# Daisy.net
KiCad netlist of a schematic drawn in EasyEDA Pro
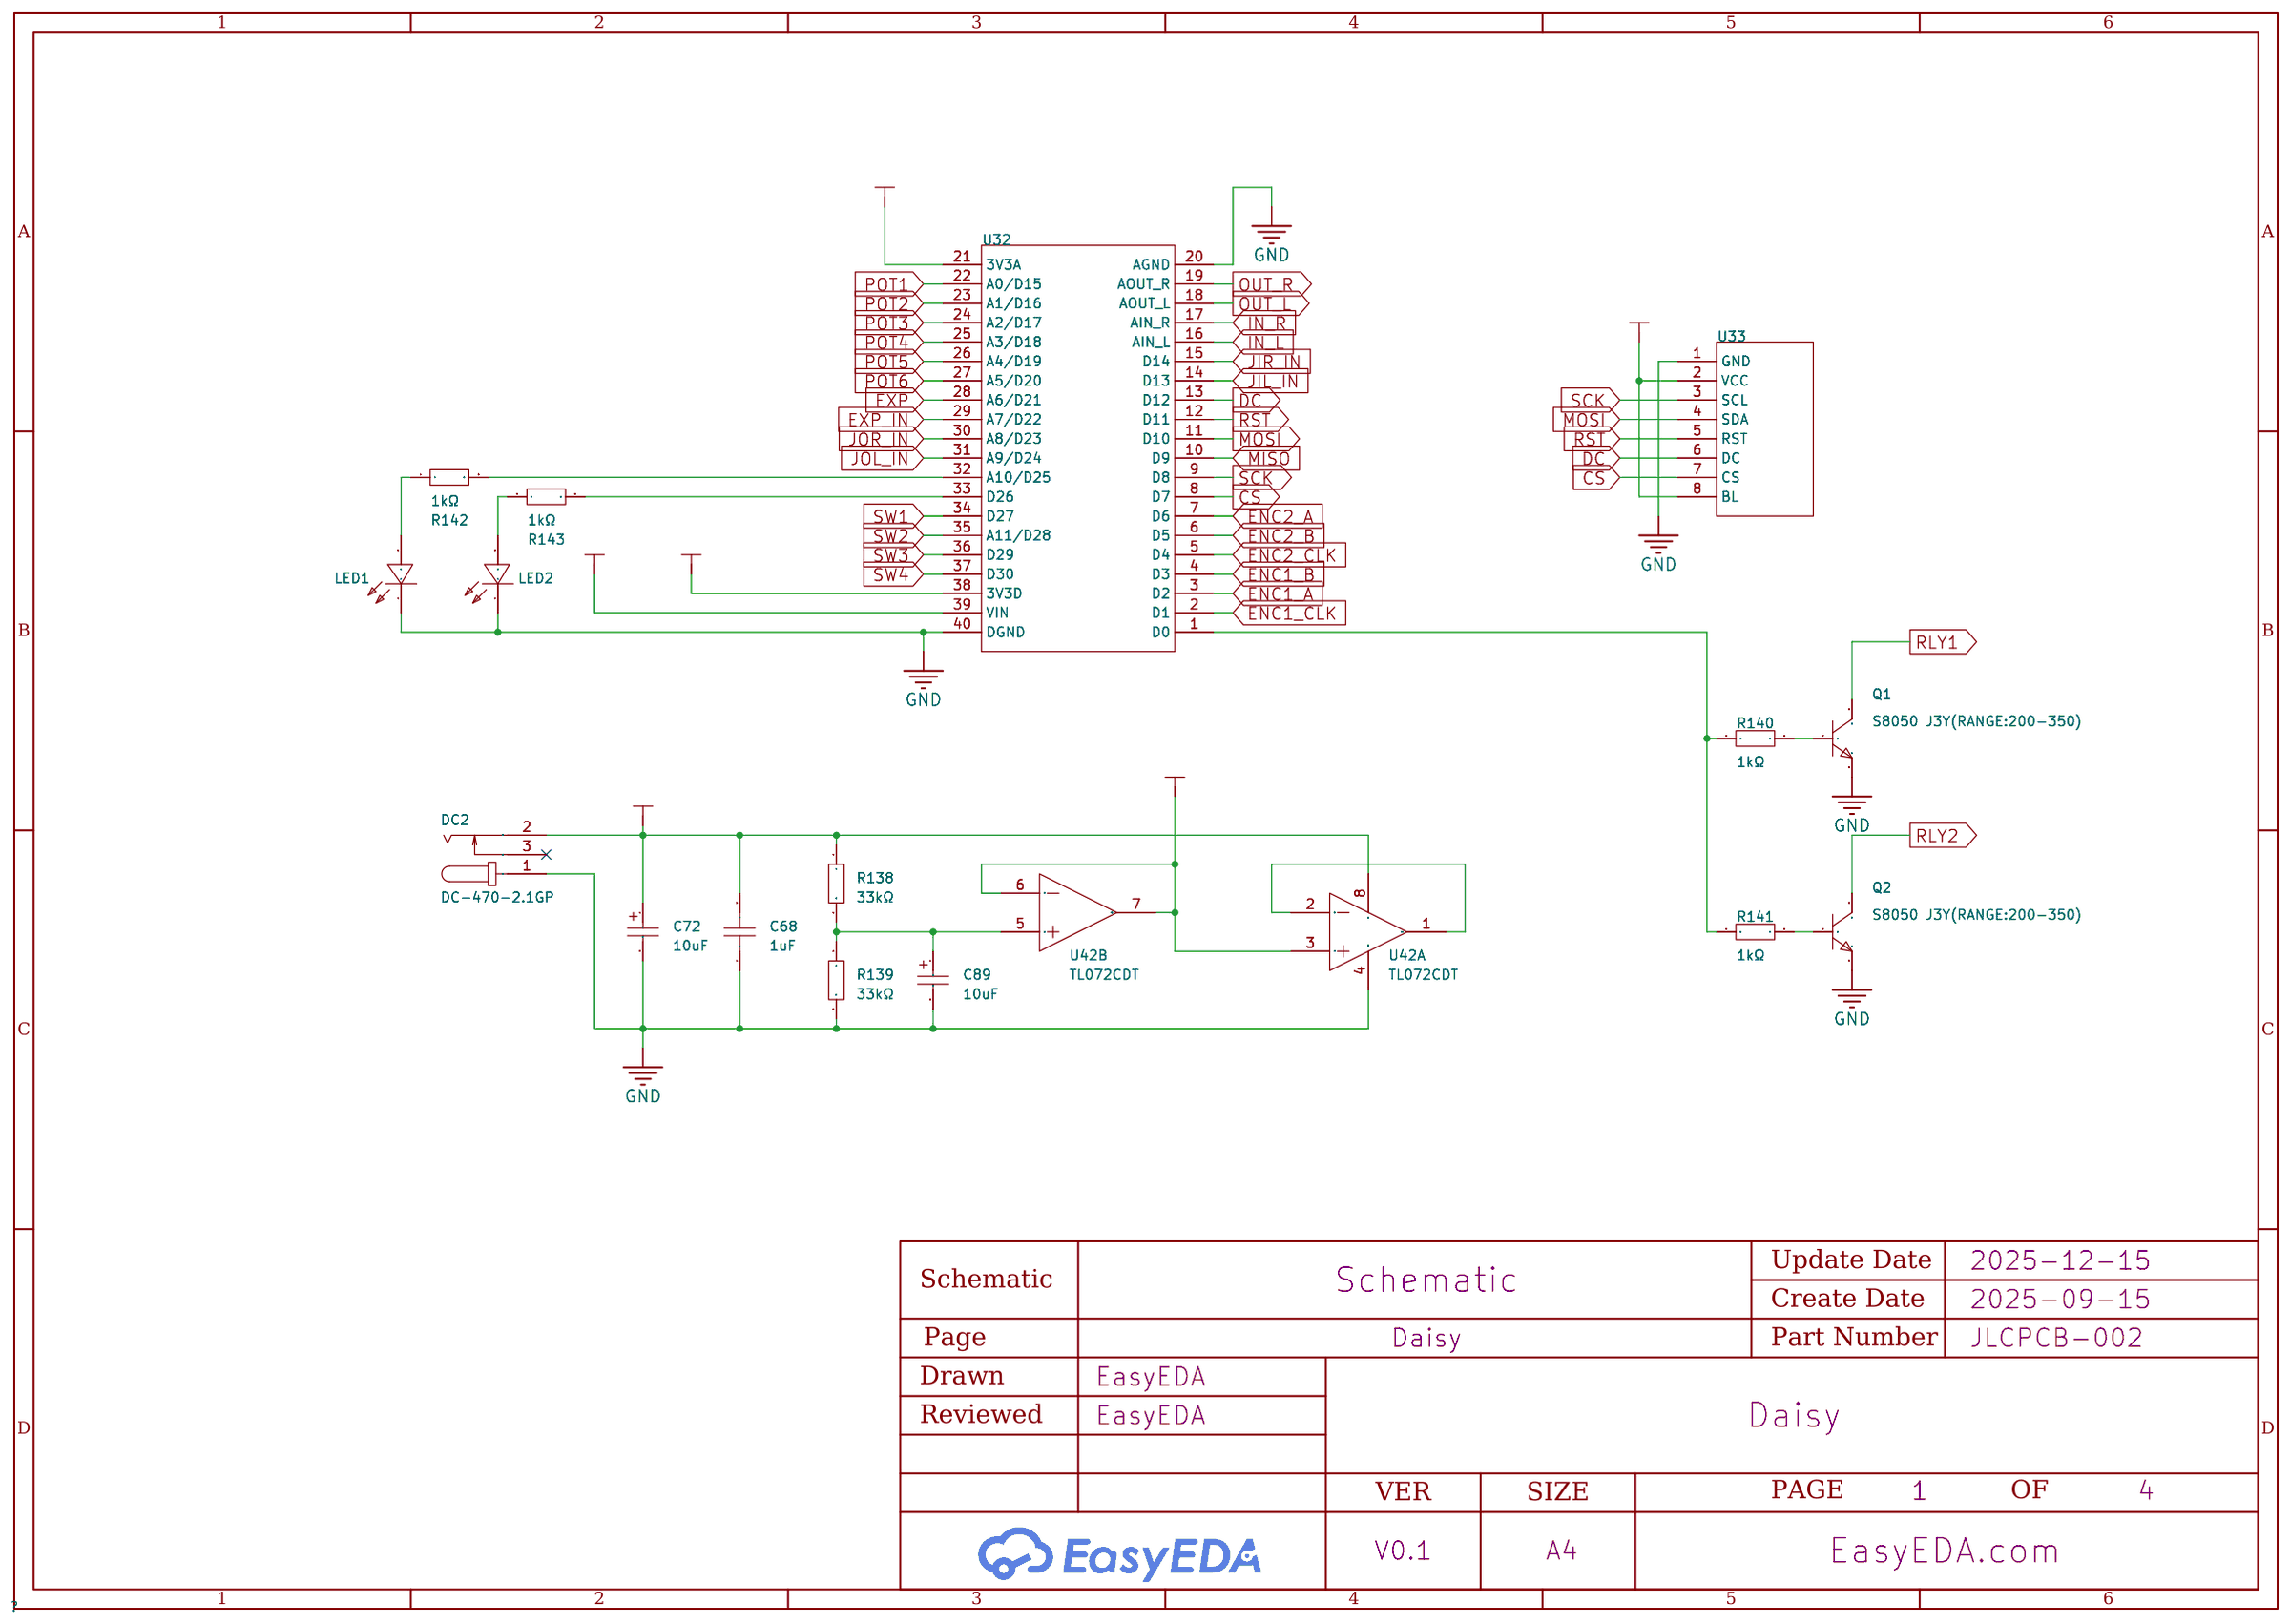
[diagram p0: Daisy]
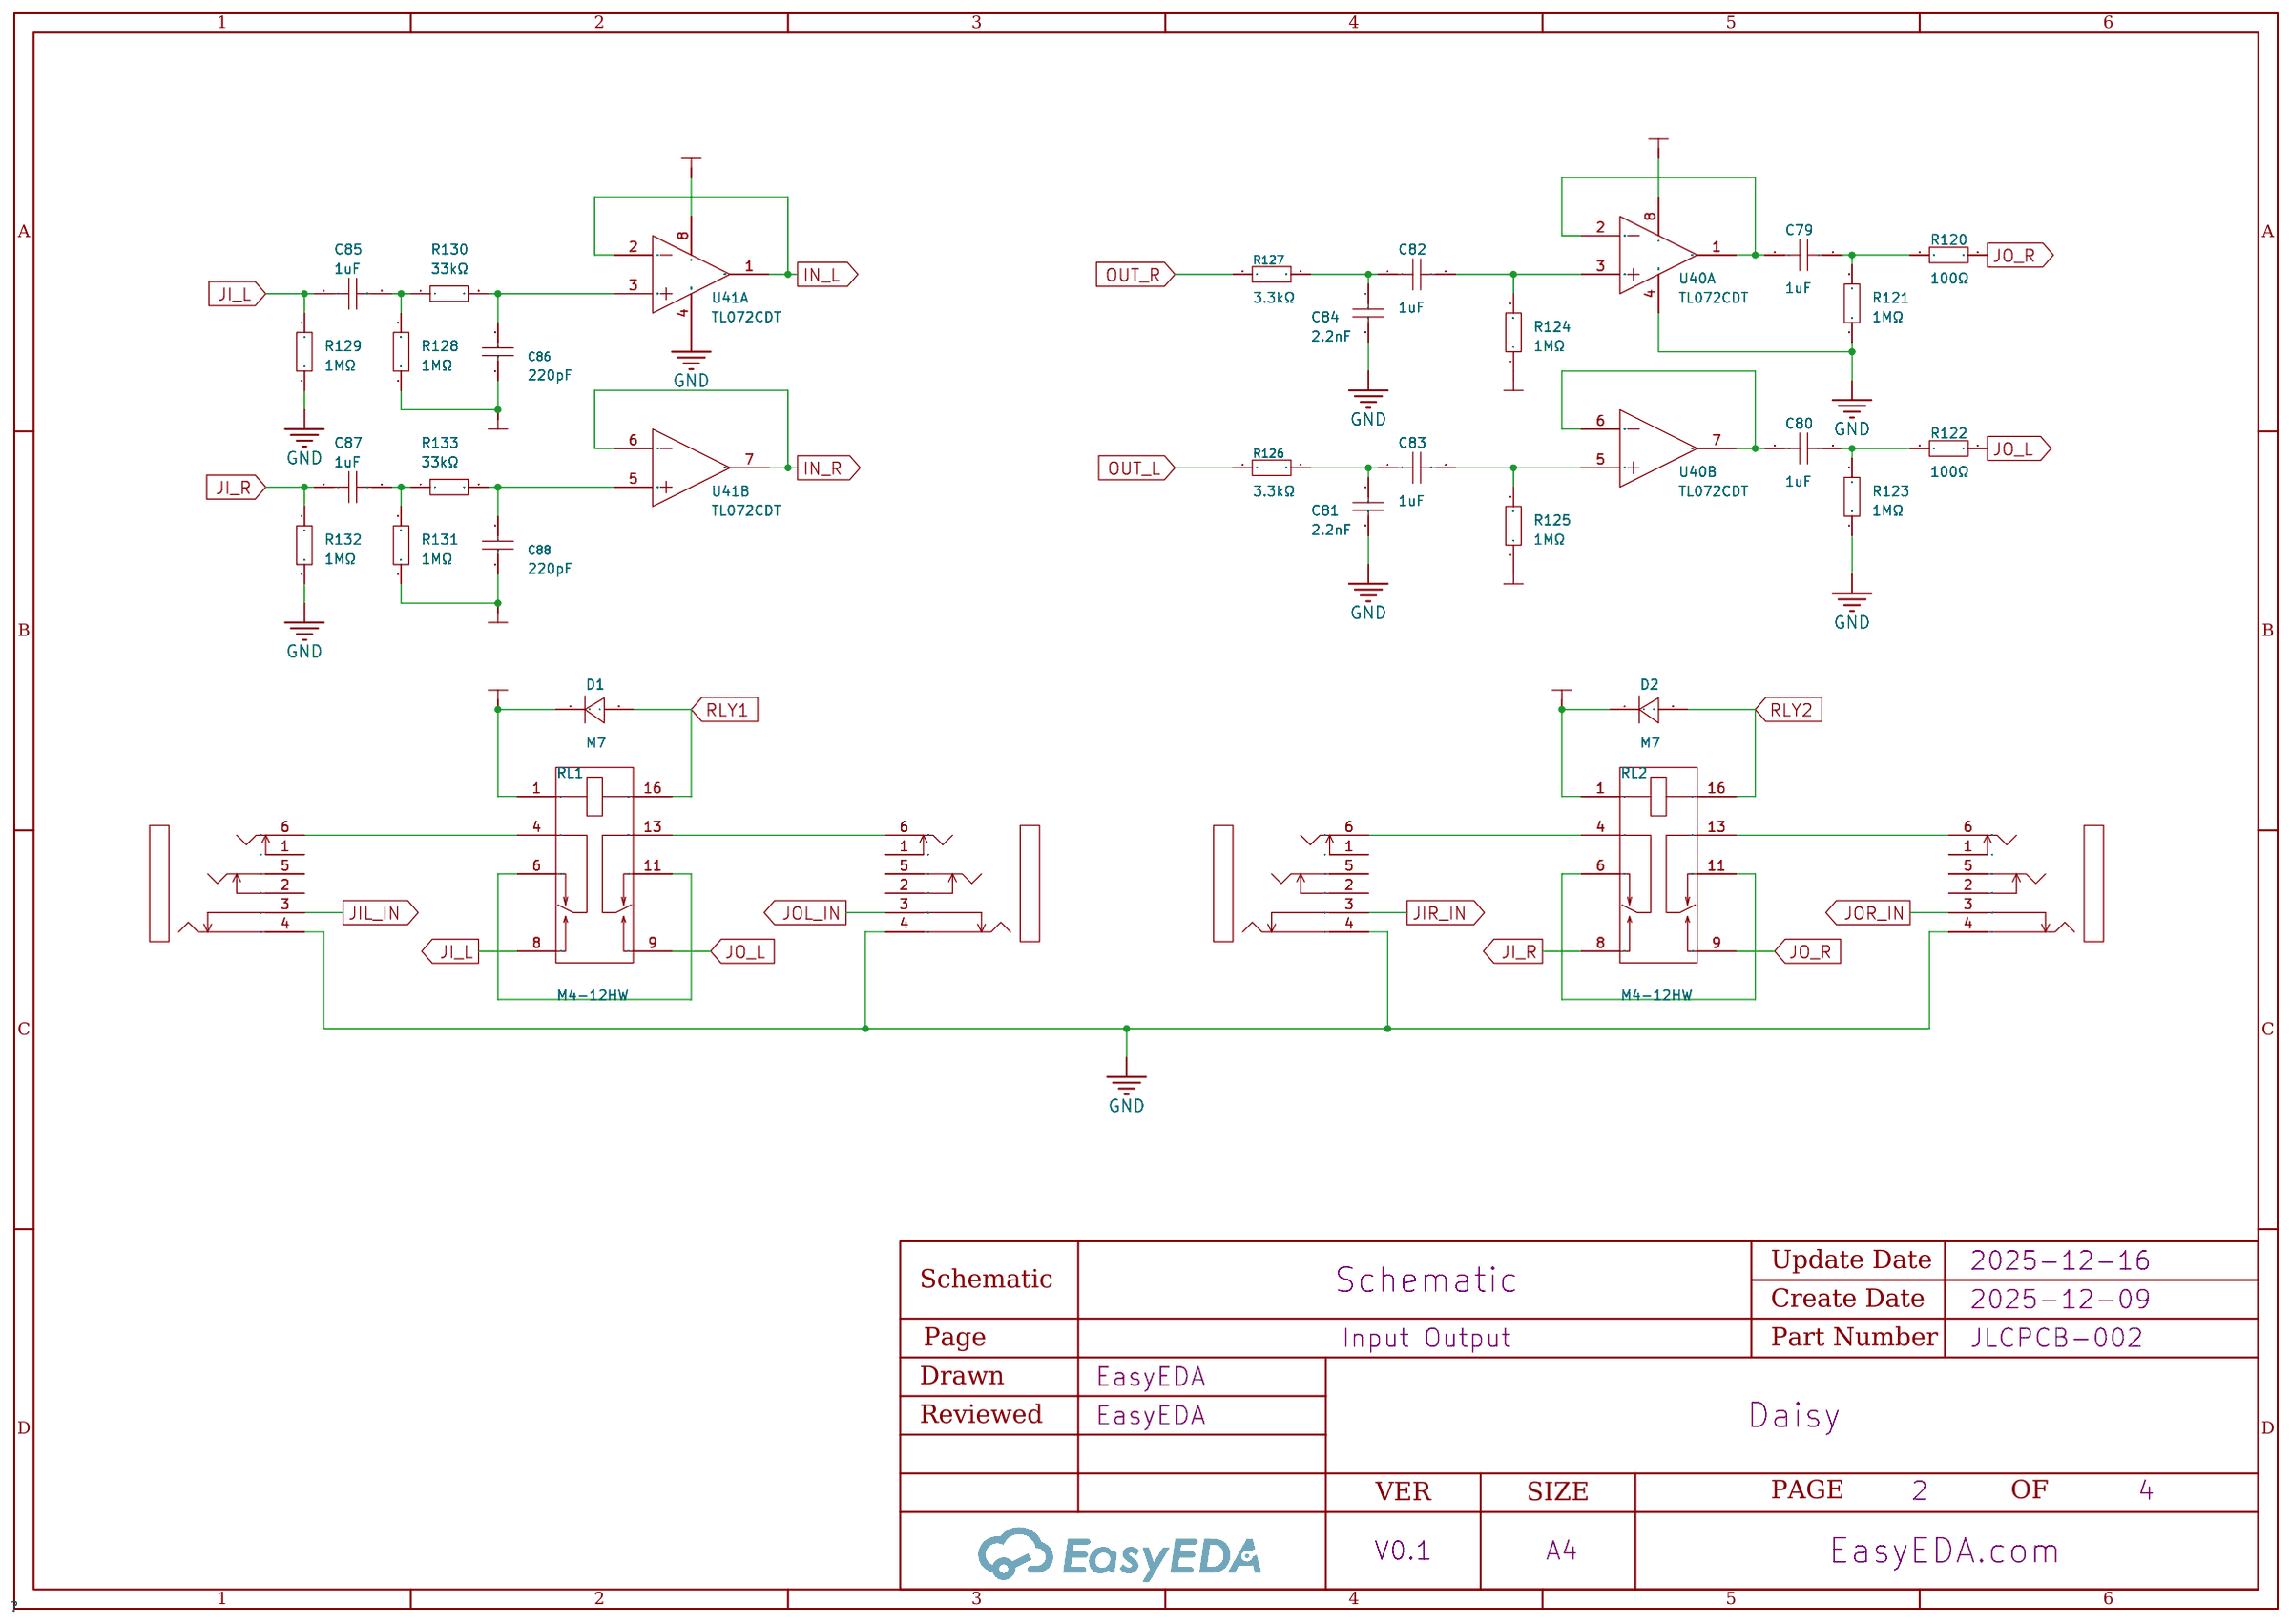
[diagram p1: Input Output]
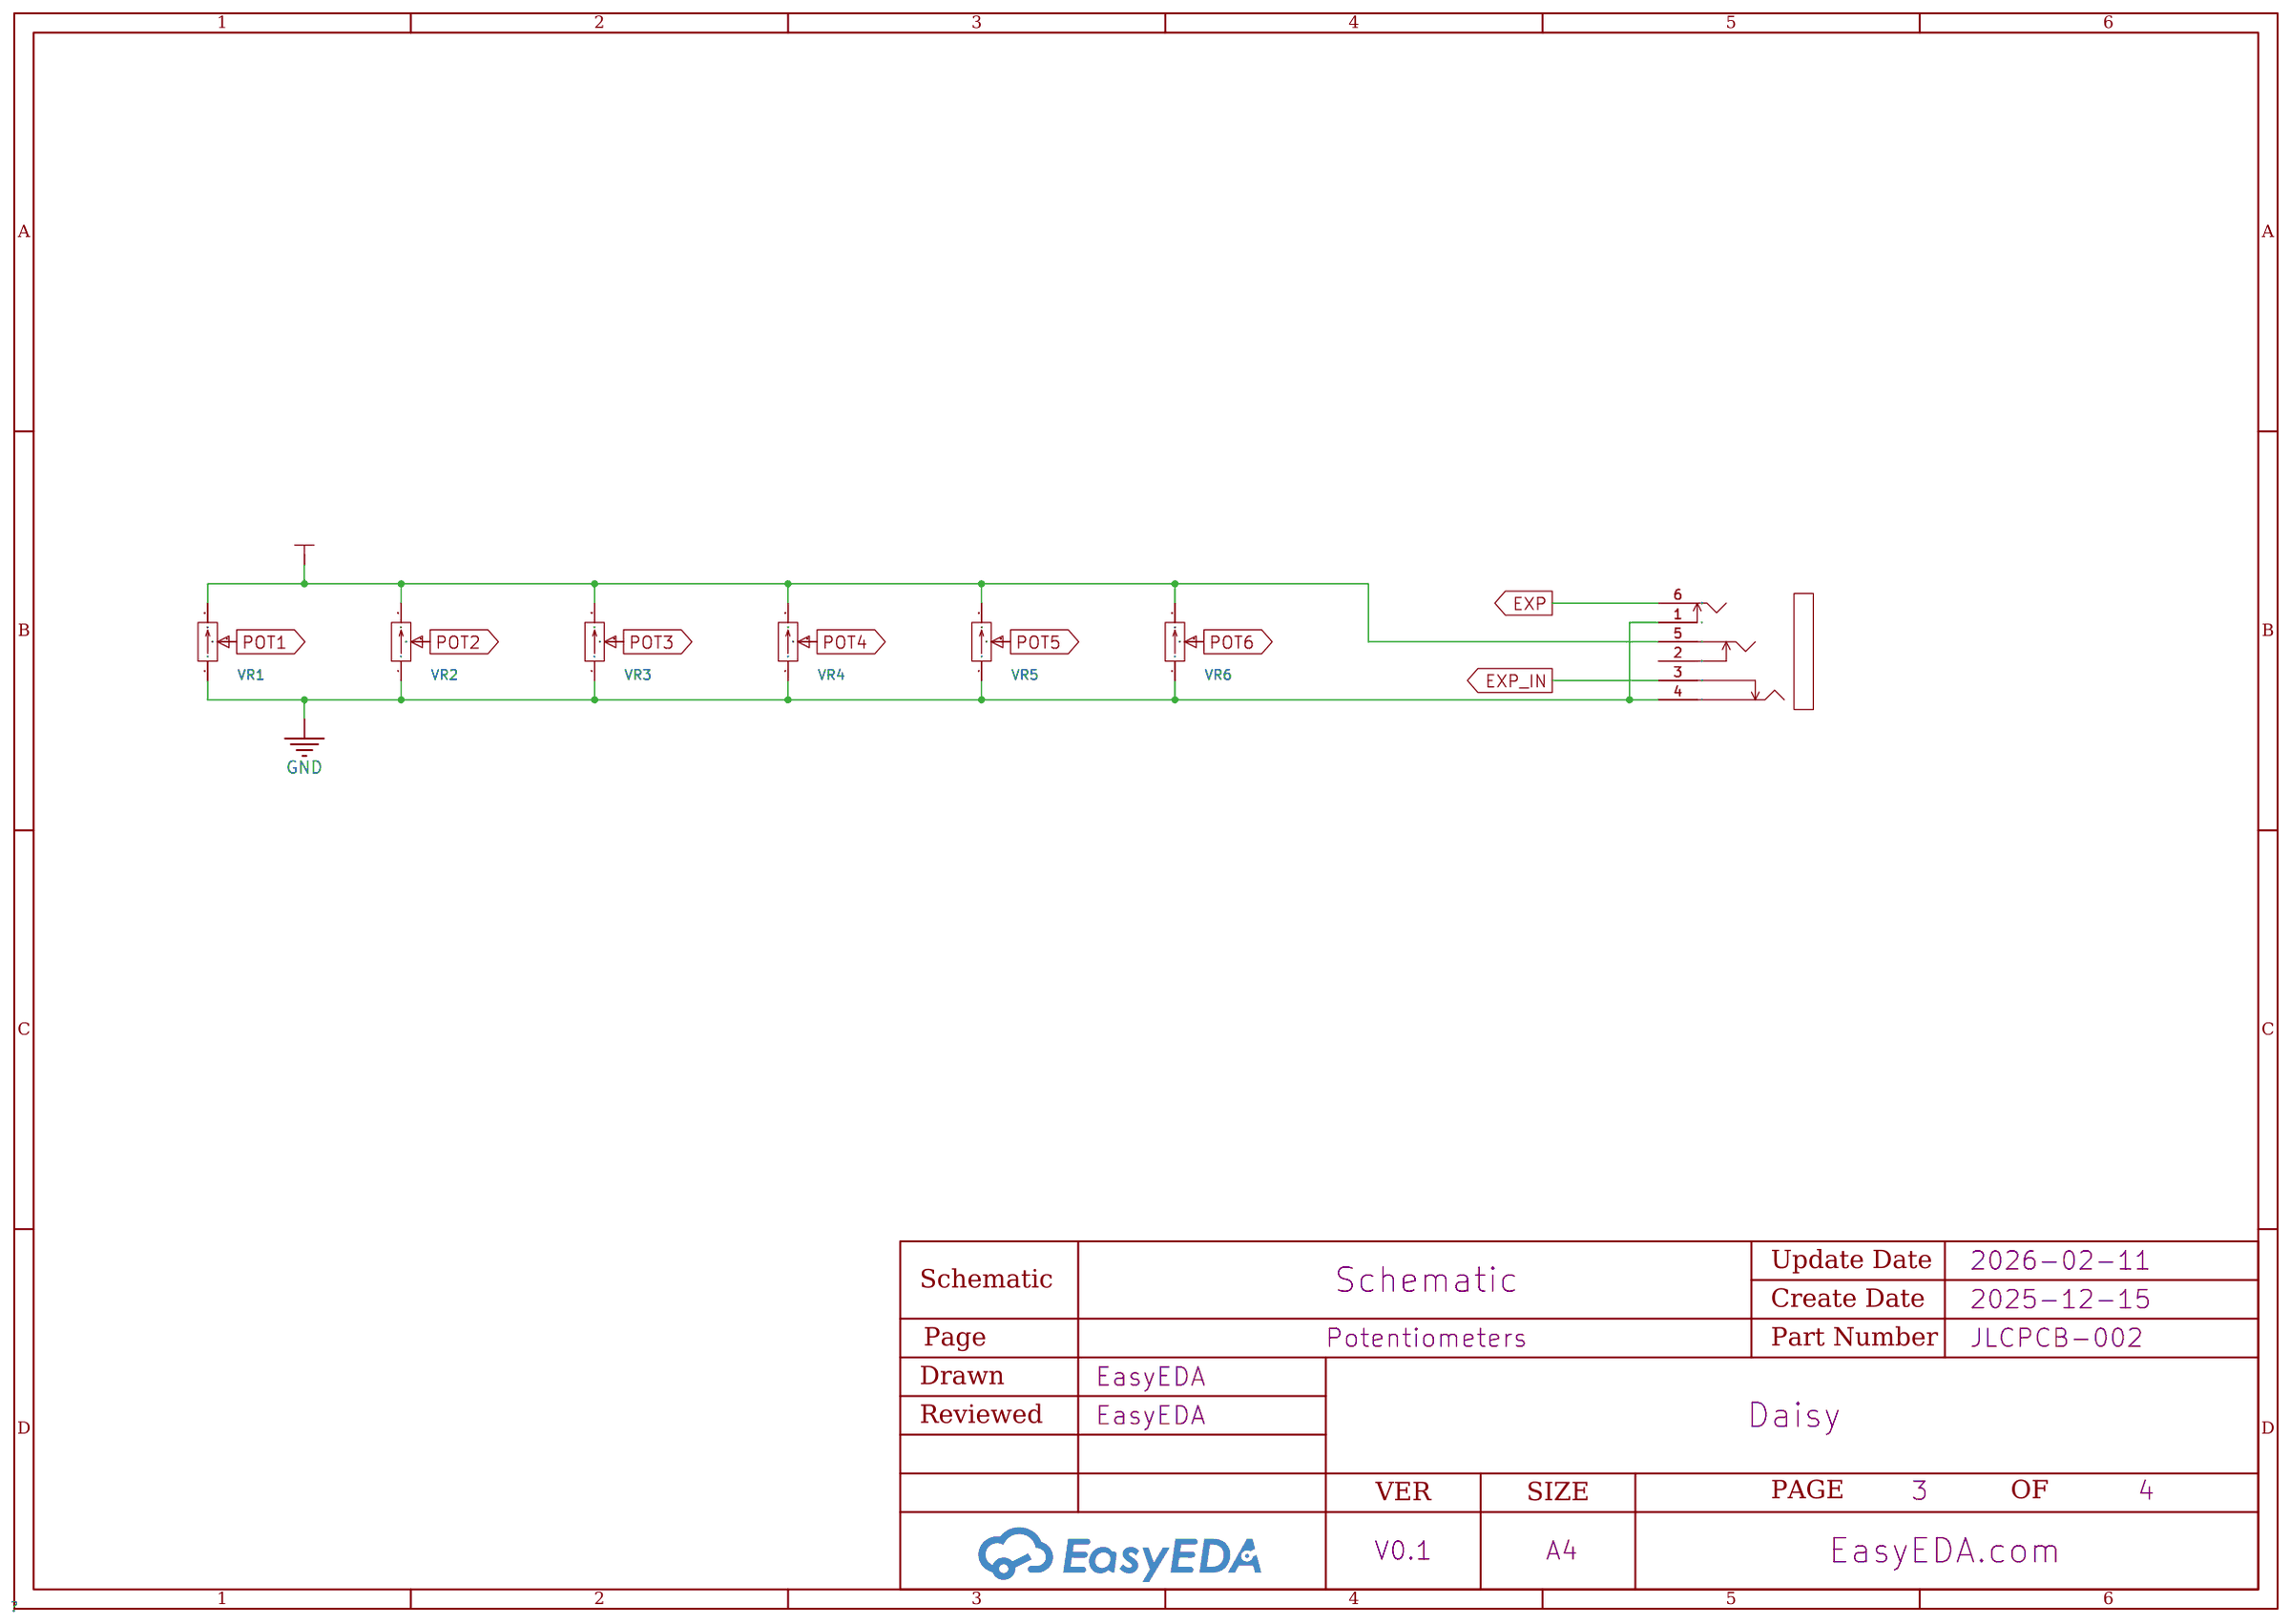
[diagram p2: Potentiometers]
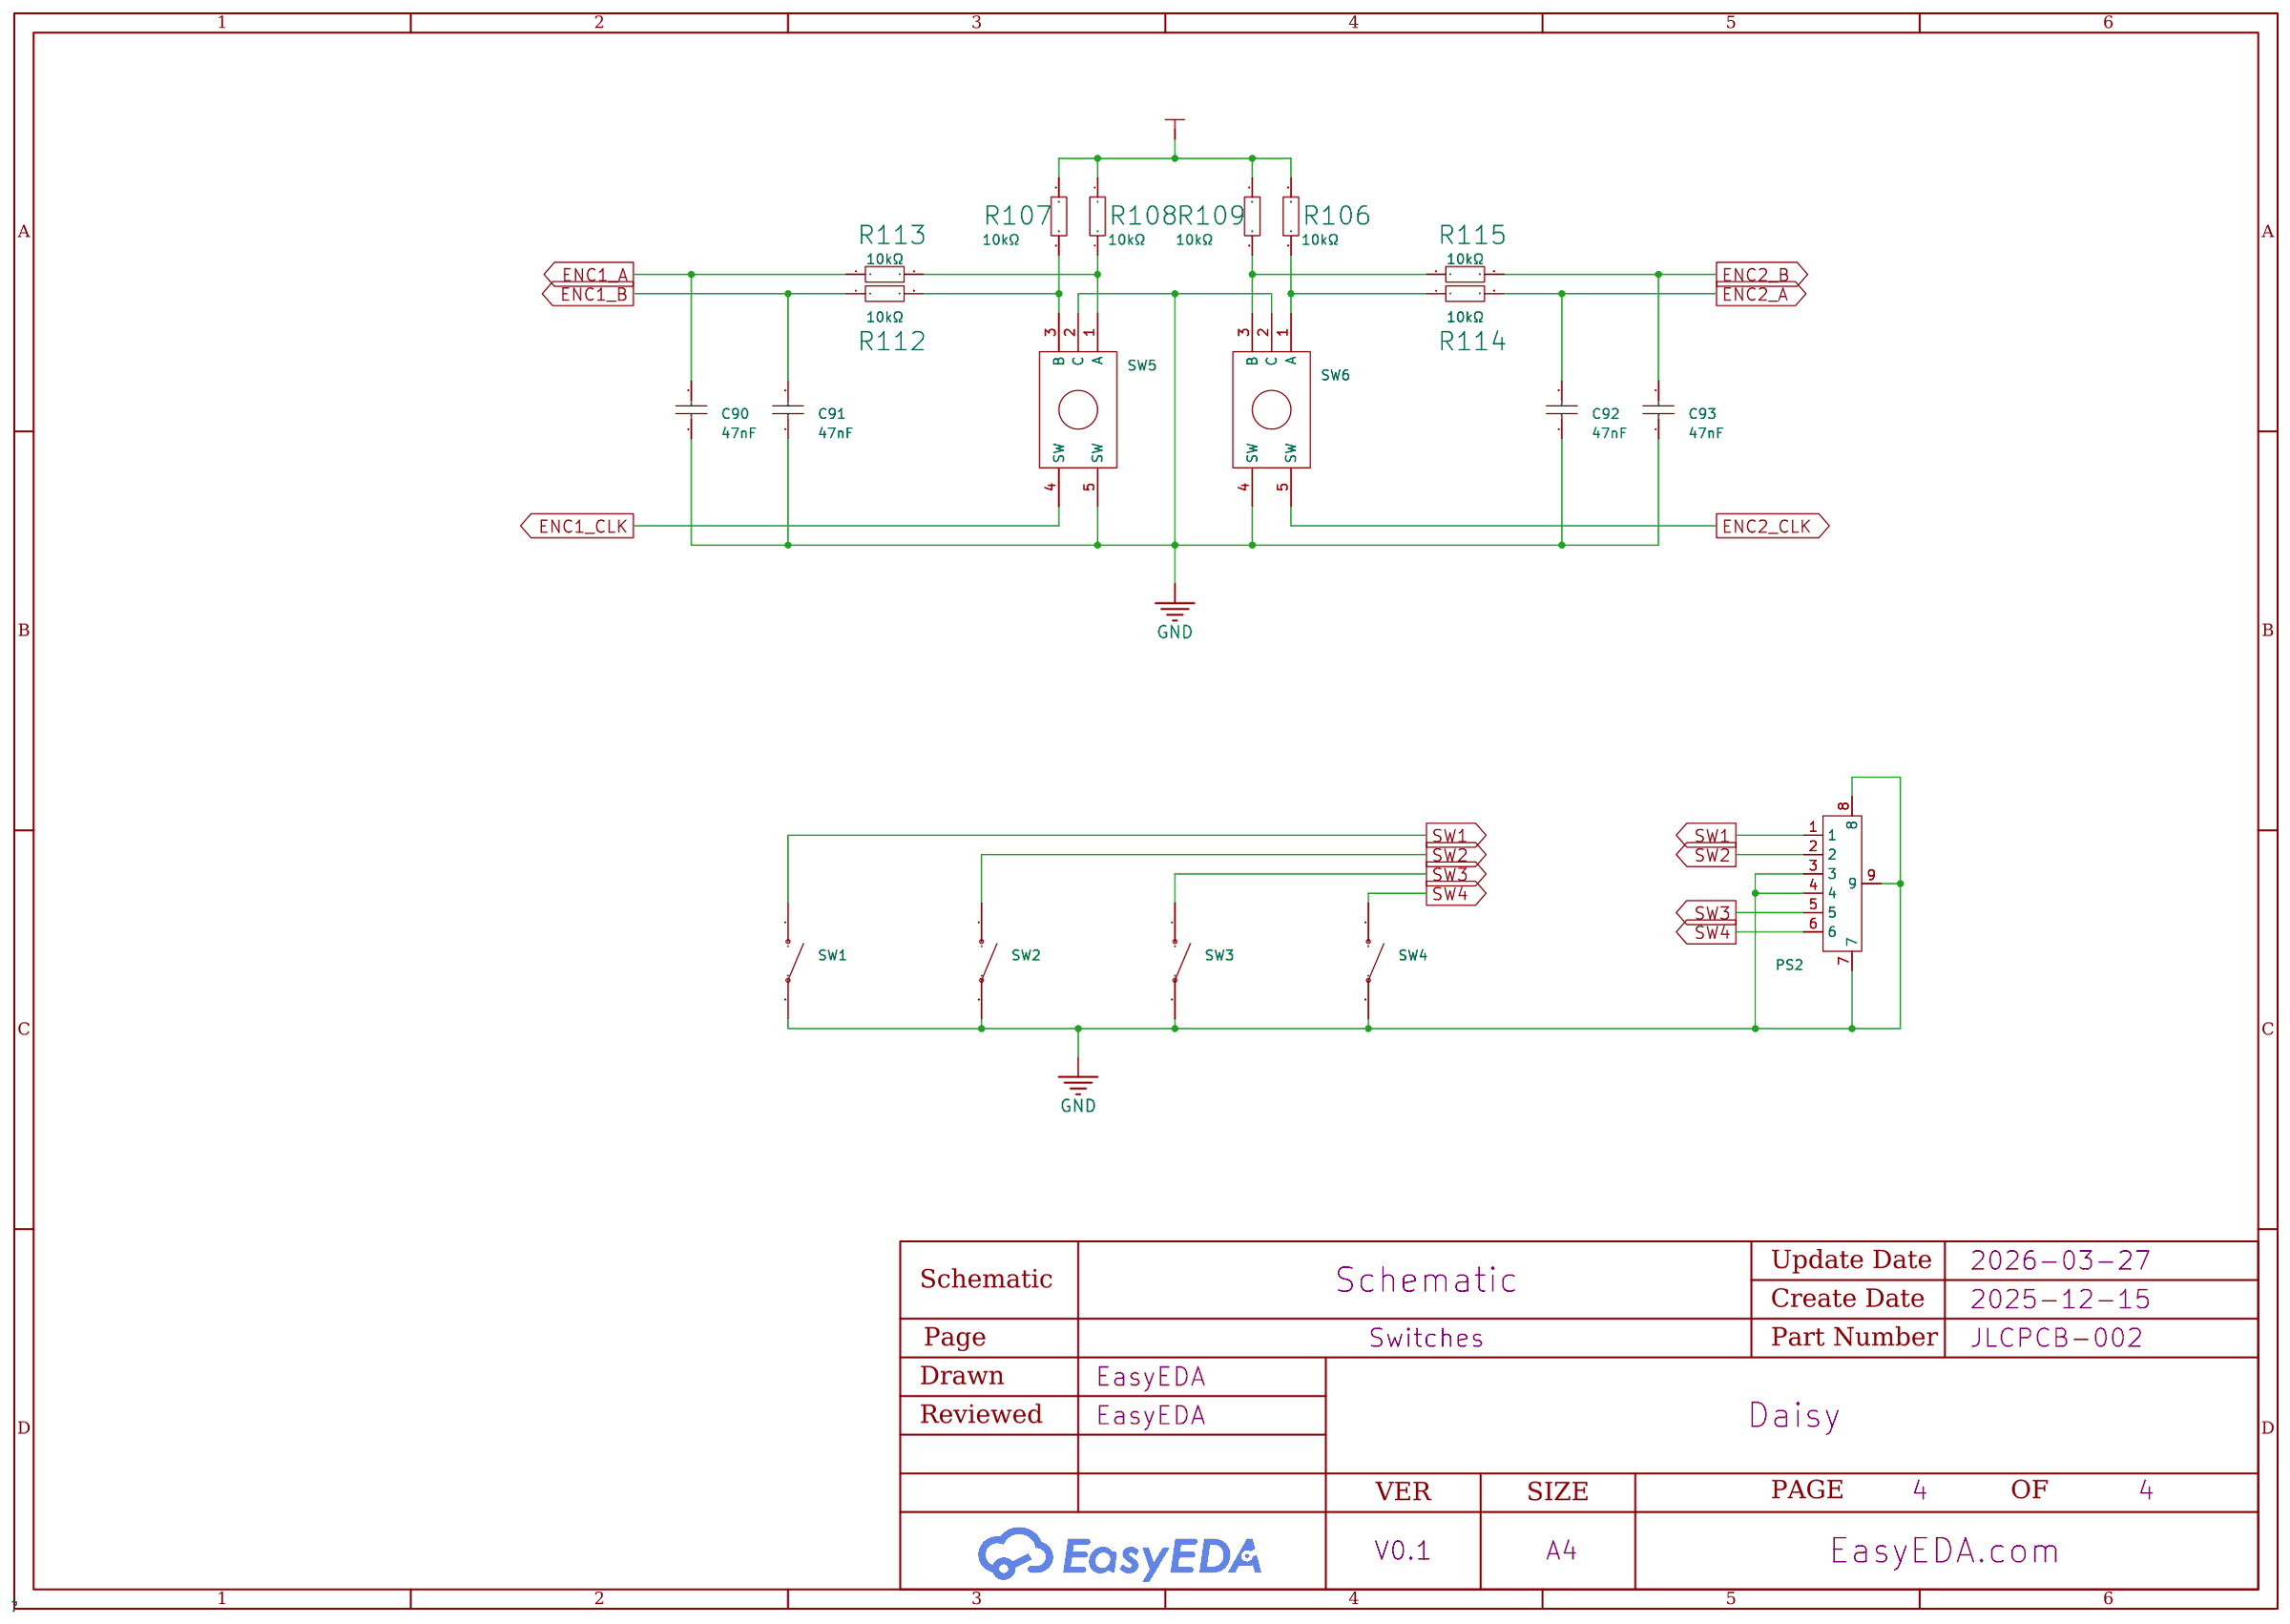
[diagram p3: Switches]

(export (version "E")
  (design (tool "Eeschema 10.0.6"))
  (components
    (comp (ref "C68")
      (value "1uF")
      (fields
        (field (name "Manufacturer Part") "CL10A105KB8NNNC")
        (field (name "Manufacturer") "SAMSUNG(三星)")
      )
      (libsource (lib "easyedapro") (part "CL10A105KB8NNNC"))
    )
    (comp (ref "C72")
      (value "10uF")
      (footprint "easyedapro:CAP-SMD_L3.2-W1.6-RD-C7171")
      (fields (field (name "Manufacturer Part") "TAJA106K016RNJ") (field (name "Manufacturer") "Kyocera AVX"))
      (libsource (lib "easyedapro") (part "TAJA106K016RNJ"))
    )
    (comp (ref "C89")
      (value "10uF")
      (footprint "easyedapro:CAP-SMD_L3.2-W1.6-RD-C7171")
      (fields (field (name "Manufacturer Part") "TAJA106K016RNJ") (field (name "Manufacturer") "Kyocera AVX"))
      (libsource (lib "easyedapro") (part "TAJA106K016RNJ"))
    )
    (comp (ref "DC2")
      (value "DC-470-2.1GP")
      (footprint "easyedapro:DC-IN-TH_DC-470-2.1GP")
      (fields (field (name "Manufacturer") "GANGYUAN(港源)"))
      (libsource (lib "easyedapro") (part "DC-470-2.1GP"))
    )
    (comp (ref "LED1")
      (value "KT-0603R")
      (footprint "easyedapro:LED0603-RD")
      (fields (field (name "Manufacturer") "KENTO"))
      (libsource (lib "easyedapro") (part "KT-0603R"))
    )
    (comp (ref "LED2")
      (value "KT-0603R")
      (footprint "easyedapro:LED0603-RD")
      (fields (field (name "Manufacturer") "KENTO"))
      (libsource (lib "easyedapro") (part "KT-0603R"))
    )
    (comp (ref "Q1")
      (value "S8050 J3Y(RANGE:200-350)")
      (footprint "easyedapro:SOT-23-3_L3.0-W1.7-P0.95-LS2.9-BR")
      (fields (field (name "Manufacturer") "CJ(江苏长电/长晶)"))
      (libsource (lib "easyedapro") (part "S8050_C2146"))
    )
    (comp (ref "Q2")
      (value "S8050 J3Y(RANGE:200-350)")
      (footprint "easyedapro:SOT-23-3_L3.0-W1.7-P0.95-LS2.9-BR")
      (fields (field (name "Manufacturer") "CJ(江苏长电/长晶)"))
      (libsource (lib "easyedapro") (part "S8050_C2146"))
    )
    (comp (ref "R138")
      (value "33kΩ")
      (footprint "easyedapro:R0603")
      (fields
        (field (name "Manufacturer Part") "0603WAF3302T5E")
        (field (name "Manufacturer") "UNI-ROYAL(厚声)")
      )
      (libsource (lib "easyedapro") (part "Res"))
    )
    (comp (ref "R139")
      (value "33kΩ")
      (footprint "easyedapro:R0603")
      (fields
        (field (name "Manufacturer Part") "0603WAF3302T5E")
        (field (name "Manufacturer") "UNI-ROYAL(厚声)")
      )
      (libsource (lib "easyedapro") (part "Res"))
    )
    (comp (ref "R140")
      (value "1kΩ")
      (footprint "easyedapro:R0603")
      (fields
        (field (name "Manufacturer Part") "0603WAF1001T5E")
        (field (name "Manufacturer") "UNI-ROYAL(厚声)")
      )
      (libsource (lib "easyedapro") (part "0603WAF1001T5E"))
    )
    (comp (ref "R141")
      (value "1kΩ")
      (footprint "easyedapro:R0603")
      (fields
        (field (name "Manufacturer Part") "0603WAF1001T5E")
        (field (name "Manufacturer") "UNI-ROYAL(厚声)")
      )
      (libsource (lib "easyedapro") (part "0603WAF1001T5E"))
    )
    (comp (ref "R142")
      (value "1kΩ")
      (footprint "easyedapro:R0603")
      (fields
        (field (name "Manufacturer Part") "0603WAF1001T5E")
        (field (name "Manufacturer") "UNI-ROYAL(厚声)")
      )
      (libsource (lib "easyedapro") (part "0603WAF1001T5E"))
    )
    (comp (ref "R143")
      (value "1kΩ")
      (footprint "easyedapro:R0603")
      (fields
        (field (name "Manufacturer Part") "0603WAF1001T5E")
        (field (name "Manufacturer") "UNI-ROYAL(厚声)")
      )
      (libsource (lib "easyedapro") (part "0603WAF1001T5E"))
    )
    (comp (ref "U32")
      (value "~")
      (footprint "easyedapro:Daisy Seed")
      (libsource (lib "easyedapro") (part "Daisy Seed"))
    )
    (comp (ref "U33")
      (value "~")
      (footprint "easyedapro:2.4 TFT Display")
      (libsource (lib "easyedapro") (part "LCD Display 2.4"))
    )
    (comp (ref "U42")
      (value "TL072CDT")
      (footprint "easyedapro:SOIC-8_L4.9-W3.9-P1.27-LS6.0-BL")
      (fields (field (name "Manufacturer") "ST(意法半导体)"))
      (libsource (lib "easyedapro") (part "NE5532DR"))
    )
    (comp (ref "C79")
      (value "1uF")
      (fields
        (field (name "Manufacturer Part") "CL10A105KB8NNNC")
        (field (name "Manufacturer") "SAMSUNG(三星)")
      )
      (libsource (lib "easyedapro") (part "CL10A105KB8NNNC"))
    )
    (comp (ref "C80")
      (value "1uF")
      (fields
        (field (name "Manufacturer Part") "CL10A105KB8NNNC")
        (field (name "Manufacturer") "SAMSUNG(三星)")
      )
      (libsource (lib "easyedapro") (part "CL10A105KB8NNNC"))
    )
    (comp (ref "C81")
      (value "2.2nF")
      (footprint "easyedapro:C0603")
      (fields (field (name "Manufacturer Part") "0603B222K500NT") (field (name "Manufacturer") "FH(风华)"))
      (libsource (lib "easyedapro") (part "0603B222K500NT"))
    )
    (comp (ref "C82")
      (value "1uF")
      (fields
        (field (name "Manufacturer Part") "CL10A105KB8NNNC")
        (field (name "Manufacturer") "SAMSUNG(三星)")
      )
      (libsource (lib "easyedapro") (part "CL10A105KB8NNNC"))
    )
    (comp (ref "C83")
      (value "1uF")
      (fields
        (field (name "Manufacturer Part") "CL10A105KB8NNNC")
        (field (name "Manufacturer") "SAMSUNG(三星)")
      )
      (libsource (lib "easyedapro") (part "CL10A105KB8NNNC"))
    )
    (comp (ref "C84")
      (value "2.2nF")
      (footprint "easyedapro:C0603")
      (fields (field (name "Manufacturer Part") "0603B222K500NT") (field (name "Manufacturer") "FH(风华)"))
      (libsource (lib "easyedapro") (part "0603B222K500NT"))
    )
    (comp (ref "C85")
      (value "1uF")
      (fields
        (field (name "Manufacturer Part") "CL10A105KB8NNNC")
        (field (name "Manufacturer") "SAMSUNG(三星)")
      )
      (libsource (lib "easyedapro") (part "CL10A105KB8NNNC"))
    )
    (comp (ref "C86")
      (value "220pF")
      (footprint "easyedapro:C0603")
      (fields
        (field (name "Manufacturer Part") "CL10B221KB8NNNC")
        (field (name "Manufacturer") "SAMSUNG(三星)")
      )
      (libsource (lib "easyedapro") (part "CL10B221KB8NNNC"))
    )
    (comp (ref "C87")
      (value "1uF")
      (fields
        (field (name "Manufacturer Part") "CL10A105KB8NNNC")
        (field (name "Manufacturer") "SAMSUNG(三星)")
      )
      (libsource (lib "easyedapro") (part "CL10A105KB8NNNC"))
    )
    (comp (ref "C88")
      (value "220pF")
      (footprint "easyedapro:C0603")
      (fields
        (field (name "Manufacturer Part") "CL10B221KB8NNNC")
        (field (name "Manufacturer") "SAMSUNG(三星)")
      )
      (libsource (lib "easyedapro") (part "CL10B221KB8NNNC"))
    )
    (comp (ref "D1")
      (value "M7")
      (footprint "easyedapro:SMA_L4.3-W2.6-LS5.2-RD")
      (fields (field (name "Manufacturer") "MDD(辰达半导体)"))
      (libsource (lib "easyedapro") (part "M7_C95872"))
    )
    (comp (ref "D2")
      (value "M7")
      (footprint "easyedapro:SMA_L4.3-W2.6-LS5.2-RD")
      (fields (field (name "Manufacturer") "MDD(辰达半导体)"))
      (libsource (lib "easyedapro") (part "M7_C95872"))
    )
    (comp (ref "J1")
      (value "~")
      (footprint "easyedapro:Stereo Switched Jack")
      (libsource (lib "easyedapro") (part "Stereo Switched Jack Socket"))
    )
    (comp (ref "J2")
      (value "~")
      (footprint "easyedapro:Stereo Switched Jack")
      (libsource (lib "easyedapro") (part "Stereo Switched Jack Socket"))
    )
    (comp (ref "J3")
      (value "~")
      (footprint "easyedapro:Stereo Switched Jack")
      (libsource (lib "easyedapro") (part "Stereo Switched Jack Socket"))
    )
    (comp (ref "J4")
      (value "~")
      (footprint "easyedapro:Stereo Switched Jack")
      (libsource (lib "easyedapro") (part "Stereo Switched Jack Socket"))
    )
    (comp (ref "R120")
      (value "100Ω")
      (footprint "easyedapro:R0603")
      (fields
        (field (name "Manufacturer Part") "0603WAF1000T5E")
        (field (name "Manufacturer") "UNI-ROYAL(厚声)")
      )
      (libsource (lib "easyedapro") (part "Res"))
    )
    (comp (ref "R121")
      (value "1MΩ")
      (footprint "easyedapro:R0603")
      (fields
        (field (name "Manufacturer Part") "0603WAF1004T5E")
        (field (name "Manufacturer") "UNI-ROYAL(厚声)")
      )
      (libsource (lib "easyedapro") (part "Res"))
    )
    (comp (ref "R122")
      (value "100Ω")
      (footprint "easyedapro:R0603")
      (fields
        (field (name "Manufacturer Part") "0603WAF1000T5E")
        (field (name "Manufacturer") "UNI-ROYAL(厚声)")
      )
      (libsource (lib "easyedapro") (part "Res"))
    )
    (comp (ref "R123")
      (value "1MΩ")
      (footprint "easyedapro:R0603")
      (fields
        (field (name "Manufacturer Part") "0603WAF1004T5E")
        (field (name "Manufacturer") "UNI-ROYAL(厚声)")
      )
      (libsource (lib "easyedapro") (part "Res"))
    )
    (comp (ref "R124")
      (value "1MΩ")
      (footprint "easyedapro:R0603")
      (fields
        (field (name "Manufacturer Part") "0603WAF1004T5E")
        (field (name "Manufacturer") "UNI-ROYAL(厚声)")
      )
      (libsource (lib "easyedapro") (part "Res"))
    )
    (comp (ref "R125")
      (value "1MΩ")
      (footprint "easyedapro:R0603")
      (fields
        (field (name "Manufacturer Part") "0603WAF1004T5E")
        (field (name "Manufacturer") "UNI-ROYAL(厚声)")
      )
      (libsource (lib "easyedapro") (part "Res"))
    )
    (comp (ref "R126")
      (value "3.3kΩ")
      (footprint "easyedapro:R0603")
      (fields
        (field (name "Manufacturer Part") "0603WAF3301T5E")
        (field (name "Manufacturer") "UNI-ROYAL(厚声)")
      )
      (libsource (lib "easyedapro") (part "0603WAF3301T5E"))
    )
    (comp (ref "R127")
      (value "3.3kΩ")
      (footprint "easyedapro:R0603")
      (fields
        (field (name "Manufacturer Part") "0603WAF3301T5E")
        (field (name "Manufacturer") "UNI-ROYAL(厚声)")
      )
      (libsource (lib "easyedapro") (part "0603WAF3301T5E"))
    )
    (comp (ref "R128")
      (value "1MΩ")
      (footprint "easyedapro:R0603")
      (fields
        (field (name "Manufacturer Part") "0603WAF1004T5E")
        (field (name "Manufacturer") "UNI-ROYAL(厚声)")
      )
      (libsource (lib "easyedapro") (part "Res"))
    )
    (comp (ref "R129")
      (value "1MΩ")
      (footprint "easyedapro:R0603")
      (fields
        (field (name "Manufacturer Part") "0603WAF1004T5E")
        (field (name "Manufacturer") "UNI-ROYAL(厚声)")
      )
      (libsource (lib "easyedapro") (part "Res"))
    )
    (comp (ref "R130")
      (value "33kΩ")
      (footprint "easyedapro:R0603")
      (fields
        (field (name "Manufacturer Part") "0603WAF3302T5E")
        (field (name "Manufacturer") "UNI-ROYAL(厚声)")
      )
      (libsource (lib "easyedapro") (part "Res"))
    )
    (comp (ref "R131")
      (value "1MΩ")
      (footprint "easyedapro:R0603")
      (fields
        (field (name "Manufacturer Part") "0603WAF1004T5E")
        (field (name "Manufacturer") "UNI-ROYAL(厚声)")
      )
      (libsource (lib "easyedapro") (part "Res"))
    )
    (comp (ref "R132")
      (value "1MΩ")
      (footprint "easyedapro:R0603")
      (fields
        (field (name "Manufacturer Part") "0603WAF1004T5E")
        (field (name "Manufacturer") "UNI-ROYAL(厚声)")
      )
      (libsource (lib "easyedapro") (part "Res"))
    )
    (comp (ref "R133")
      (value "33kΩ")
      (footprint "easyedapro:R0603")
      (fields
        (field (name "Manufacturer Part") "0603WAF3302T5E")
        (field (name "Manufacturer") "UNI-ROYAL(厚声)")
      )
      (libsource (lib "easyedapro") (part "Res"))
    )
    (comp (ref "RL1")
      (value "M4-12HW")
      (footprint "easyedapro:RELAYS-TH_M4-XXHXX")
      (fields (field (name "Manufacturer") "NF(福特)"))
      (libsource (lib "easyedapro") (part "M4-12HW"))
    )
    (comp (ref "RL2")
      (value "M4-12HW")
      (footprint "easyedapro:RELAYS-TH_M4-XXHXX")
      (fields (field (name "Manufacturer") "NF(福特)"))
      (libsource (lib "easyedapro") (part "M4-12HW"))
    )
    (comp (ref "U40")
      (value "TL072CDT")
      (footprint "easyedapro:SOIC-8_L4.9-W3.9-P1.27-LS6.0-BL")
      (fields (field (name "Manufacturer") "ST(意法半导体)"))
      (libsource (lib "easyedapro") (part "NE5532DR"))
    )
    (comp (ref "U41")
      (value "TL072CDT")
      (footprint "easyedapro:SOIC-8_L4.9-W3.9-P1.27-LS6.0-BL")
      (fields (field (name "Manufacturer") "ST(意法半导体)"))
      (libsource (lib "easyedapro") (part "NE5532DR"))
    )
    (comp (ref "J5")
      (value "~")
      (footprint "easyedapro:Stereo Switched Jack")
      (libsource (lib "easyedapro") (part "Stereo Switched Jack Socket"))
    )
    (comp (ref "VR1")
      (value "~")
      (footprint "easyedapro:RD901F")
      (libsource (lib "easyedapro") (part "RD901F"))
    )
    (comp (ref "VR2")
      (value "~")
      (footprint "easyedapro:RD901F")
      (libsource (lib "easyedapro") (part "RD901F"))
    )
    (comp (ref "VR3")
      (value "~")
      (footprint "easyedapro:RD901F")
      (libsource (lib "easyedapro") (part "RD901F"))
    )
    (comp (ref "VR4")
      (value "~")
      (footprint "easyedapro:RD901F")
      (libsource (lib "easyedapro") (part "RD901F"))
    )
    (comp (ref "VR5")
      (value "~")
      (footprint "easyedapro:RD901F")
      (libsource (lib "easyedapro") (part "RD901F"))
    )
    (comp (ref "VR6")
      (value "~")
      (footprint "easyedapro:RD901F")
      (libsource (lib "easyedapro") (part "RD901F"))
    )
    (comp (ref "C90")
      (value "47nF")
      (footprint "easyedapro:C0603")
      (description "Capacitance:47nF Tolerance:±10% Tolerance:±10% Voltage Rating:50V Temperature Coefficient:X7R")
      (fields
        (field (name "Manufacturer Part") "CL10B473KB8NNNC")
        (field (name "Manufacturer") "SAMSUNG(三星)")
      )
      (libsource (lib "easyedapro") (part "CL10B473KB8NNNC"))
    )
    (comp (ref "C91")
      (value "47nF")
      (footprint "easyedapro:C0603")
      (description "Capacitance:47nF Tolerance:±10% Tolerance:±10% Voltage Rating:50V Temperature Coefficient:X7R")
      (fields
        (field (name "Manufacturer Part") "CL10B473KB8NNNC")
        (field (name "Manufacturer") "SAMSUNG(三星)")
      )
      (libsource (lib "easyedapro") (part "CL10B473KB8NNNC"))
    )
    (comp (ref "C92")
      (value "47nF")
      (footprint "easyedapro:C0603")
      (description "Capacitance:47nF Tolerance:±10% Tolerance:±10% Voltage Rating:50V Temperature Coefficient:X7R")
      (fields
        (field (name "Manufacturer Part") "CL10B473KB8NNNC")
        (field (name "Manufacturer") "SAMSUNG(三星)")
      )
      (libsource (lib "easyedapro") (part "CL10B473KB8NNNC"))
    )
    (comp (ref "C93")
      (value "47nF")
      (footprint "easyedapro:C0603")
      (description "Capacitance:47nF Tolerance:±10% Tolerance:±10% Voltage Rating:50V Temperature Coefficient:X7R")
      (fields
        (field (name "Manufacturer Part") "CL10B473KB8NNNC")
        (field (name "Manufacturer") "SAMSUNG(三星)")
      )
      (libsource (lib "easyedapro") (part "CL10B473KB8NNNC"))
    )
    (comp (ref "PS2")
      (value "HYC03-MDC603-128B")
      (footprint "easyedapro:CONN-TH_HYC_HYC03-MDC603-128B")
      (fields (field (name "Manufacturer") "华宇创"))
      (libsource (lib "easyedapro") (part "HYC03-MDC603-128B"))
    )
    (comp (ref "R106")
      (value "10kΩ")
      (footprint "easyedapro:R0603")
      (fields
        (field (name "Manufacturer Part") "0603WAF1002T5E")
        (field (name "Manufacturer") "UNI-ROYAL(厚声)")
      )
      (libsource (lib "easyedapro") (part "0603WAF1002T5E"))
    )
    (comp (ref "R107")
      (value "10kΩ")
      (footprint "easyedapro:R0603")
      (fields
        (field (name "Manufacturer Part") "0603WAF1002T5E")
        (field (name "Manufacturer") "UNI-ROYAL(厚声)")
      )
      (libsource (lib "easyedapro") (part "0603WAF1002T5E"))
    )
    (comp (ref "R108")
      (value "10kΩ")
      (footprint "easyedapro:R0603")
      (fields
        (field (name "Manufacturer Part") "0603WAF1002T5E")
        (field (name "Manufacturer") "UNI-ROYAL(厚声)")
      )
      (libsource (lib "easyedapro") (part "0603WAF1002T5E"))
    )
    (comp (ref "R109")
      (value "10kΩ")
      (footprint "easyedapro:R0603")
      (fields
        (field (name "Manufacturer Part") "0603WAF1002T5E")
        (field (name "Manufacturer") "UNI-ROYAL(厚声)")
      )
      (libsource (lib "easyedapro") (part "0603WAF1002T5E"))
    )
    (comp (ref "R112")
      (value "10kΩ")
      (footprint "easyedapro:R0603")
      (fields
        (field (name "Manufacturer Part") "0603WAF1002T5E")
        (field (name "Manufacturer") "UNI-ROYAL(厚声)")
      )
      (libsource (lib "easyedapro") (part "0603WAF1002T5E"))
    )
    (comp (ref "R113")
      (value "10kΩ")
      (footprint "easyedapro:R0603")
      (fields
        (field (name "Manufacturer Part") "0603WAF1002T5E")
        (field (name "Manufacturer") "UNI-ROYAL(厚声)")
      )
      (libsource (lib "easyedapro") (part "0603WAF1002T5E"))
    )
    (comp (ref "R114")
      (value "10kΩ")
      (footprint "easyedapro:R0603")
      (fields
        (field (name "Manufacturer Part") "0603WAF1002T5E")
        (field (name "Manufacturer") "UNI-ROYAL(厚声)")
      )
      (libsource (lib "easyedapro") (part "0603WAF1002T5E"))
    )
    (comp (ref "R115")
      (value "10kΩ")
      (footprint "easyedapro:R0603")
      (fields
        (field (name "Manufacturer Part") "0603WAF1002T5E")
        (field (name "Manufacturer") "UNI-ROYAL(厚声)")
      )
      (libsource (lib "easyedapro") (part "0603WAF1002T5E"))
    )
    (comp (ref "SW1")
      (value "~")
      (footprint "easyedapro:Tactile Switch 6mm")
      (libsource (lib "easyedapro") (part "Tactile Switch"))
    )
    (comp (ref "SW2")
      (value "~")
      (footprint "easyedapro:Tactile Switch 6mm")
      (libsource (lib "easyedapro") (part "Tactile Switch"))
    )
    (comp (ref "SW3")
      (value "~")
      (footprint "easyedapro:Tactile Switch 6mm")
      (libsource (lib "easyedapro") (part "Tactile Switch"))
    )
    (comp (ref "SW4")
      (value "~")
      (footprint "easyedapro:Tactile Switch 6mm")
      (libsource (lib "easyedapro") (part "Tactile Switch"))
    )
    (comp (ref "SW5")
      (value "~")
      (footprint "easyedapro:12mm Encoder")
      (libsource (lib "easyedapro") (part "Rotary Encoder w Switch"))
    )
    (comp (ref "SW6")
      (value "~")
      (footprint "easyedapro:12mm Encoder")
      (libsource (lib "easyedapro") (part "Rotary Encoder w Switch"))
    )
  )
  (nets
    (net (code "1") (name "+9V") (class "Default")
      (node (ref "C68") (pin "2") (pinfunction "2_2") (pintype "unspecified"))
      (node (ref "C72") (pin "1") (pinfunction "1_1") (pintype "input"))
      (node (ref "D1") (pin "1") (pinfunction "K_1") (pintype "unspecified"))
      (node (ref "D2") (pin "1") (pinfunction "K_1") (pintype "unspecified"))
      (node (ref "DC2") (pin "2") (pinfunction "2_2") (pintype "unspecified"))
      (node (ref "R138") (pin "1") (pinfunction "1_1") (pintype "input"))
      (node (ref "RL1") (pin "1") (pinfunction "1_1") (pintype "unspecified"))
      (node (ref "RL2") (pin "1") (pinfunction "1_1") (pintype "unspecified"))
      (node (ref "U32") (pin "39") (pinfunction "VIN_39") (pintype "input"))
      (node (ref "U40") (pin "8") (pinfunction "VCC+_8") (pintype "unspecified"))
      (node (ref "U41") (pin "8") (pinfunction "VCC+_8") (pintype "unspecified"))
      (node (ref "U42") (pin "8") (pinfunction "VCC+_8") (pintype "unspecified"))
    )
    (net (code "2") (name "3V3A") (class "Default")
      (node (ref "J5") (pin "5") (pinfunction "5_5") (pintype "input"))
      (node (ref "U32") (pin "21") (pinfunction "3V3A_21") (pintype "input"))
      (node (ref "VR1") (pin "3") (pinfunction "3_3") (pintype "input"))
      (node (ref "VR2") (pin "3") (pinfunction "3_3") (pintype "input"))
      (node (ref "VR3") (pin "3") (pinfunction "3_3") (pintype "input"))
      (node (ref "VR4") (pin "3") (pinfunction "3_3") (pintype "input"))
      (node (ref "VR5") (pin "3") (pinfunction "3_3") (pintype "input"))
      (node (ref "VR6") (pin "3") (pinfunction "3_3") (pintype "input"))
    )
    (net (code "3") (name "3V3D") (class "Default")
      (node (ref "R106") (pin "1") (pinfunction "1_1") (pintype "input"))
      (node (ref "R107") (pin "1") (pinfunction "1_1") (pintype "input"))
      (node (ref "R108") (pin "1") (pinfunction "1_1") (pintype "input"))
      (node (ref "R109") (pin "1") (pinfunction "1_1") (pintype "input"))
      (node (ref "U32") (pin "38") (pinfunction "3V3D_38") (pintype "input"))
      (node (ref "U33") (pin "2") (pinfunction "VCC_2") (pintype "input"))
      (node (ref "U33") (pin "8") (pinfunction "BL_8") (pintype "input"))
    )
    (net (code "4") (name "CS") (class "Default")
      (node (ref "U32") (pin "8") (pinfunction "D7_8") (pintype "input"))
      (node (ref "U33") (pin "7") (pinfunction "CS_7") (pintype "input"))
    )
    (net (code "5") (name "DC") (class "Default")
      (node (ref "U32") (pin "13") (pinfunction "D12_13") (pintype "input"))
      (node (ref "U33") (pin "6") (pinfunction "DC_6") (pintype "input"))
    )
    (net (code "6") (name "ENC1_A") (class "Default")
      (node (ref "C90") (pin "2") (pinfunction "2_2") (pintype "input"))
      (node (ref "R113") (pin "1") (pinfunction "1_1") (pintype "input"))
      (node (ref "U32") (pin "3") (pinfunction "D2_3") (pintype "input"))
    )
    (net (code "7") (name "ENC1_B") (class "Default")
      (node (ref "C91") (pin "2") (pinfunction "2_2") (pintype "input"))
      (node (ref "R112") (pin "1") (pinfunction "1_1") (pintype "input"))
      (node (ref "U32") (pin "4") (pinfunction "D3_4") (pintype "input"))
    )
    (net (code "8") (name "ENC1_CLK") (class "Default")
      (node (ref "SW5") (pin "4") (pinfunction "SW_4") (pintype "input"))
      (node (ref "U32") (pin "2") (pinfunction "D1_2") (pintype "input"))
    )
    (net (code "9") (name "ENC2_A") (class "Default")
      (node (ref "C92") (pin "2") (pinfunction "2_2") (pintype "input"))
      (node (ref "R114") (pin "2") (pinfunction "2_2") (pintype "input"))
      (node (ref "U32") (pin "7") (pinfunction "D6_7") (pintype "input"))
    )
    (net (code "10") (name "ENC2_B") (class "Default")
      (node (ref "C93") (pin "2") (pinfunction "2_2") (pintype "input"))
      (node (ref "R115") (pin "2") (pinfunction "2_2") (pintype "input"))
      (node (ref "U32") (pin "6") (pinfunction "D5_6") (pintype "input"))
    )
    (net (code "11") (name "ENC2_CLK") (class "Default")
      (node (ref "SW6") (pin "5") (pinfunction "SW_5") (pintype "input"))
      (node (ref "U32") (pin "5") (pinfunction "D4_5") (pintype "input"))
    )
    (net (code "12") (name "EXP") (class "Default")
      (node (ref "J5") (pin "6") (pinfunction "6_6") (pintype "input"))
      (node (ref "U32") (pin "28") (pinfunction "A6/D21_28") (pintype "input"))
    )
    (net (code "13") (name "EXP_IN") (class "Default")
      (node (ref "J5") (pin "3") (pinfunction "3_3") (pintype "input"))
      (node (ref "U32") (pin "29") (pinfunction "A7/D22_29") (pintype "input"))
    )
    (net (code "14") (name "GND") (class "Default")
      (node (ref "C68") (pin "1") (pinfunction "1_1") (pintype "unspecified"))
      (node (ref "C72") (pin "2") (pinfunction "2_2") (pintype "input"))
      (node (ref "C81") (pin "2") (pinfunction "2_2") (pintype "input"))
      (node (ref "C84") (pin "2") (pinfunction "2_2") (pintype "input"))
      (node (ref "C89") (pin "2") (pinfunction "2_2") (pintype "input"))
      (node (ref "C90") (pin "1") (pinfunction "1_1") (pintype "input"))
      (node (ref "C91") (pin "1") (pinfunction "1_1") (pintype "input"))
      (node (ref "C92") (pin "1") (pinfunction "1_1") (pintype "input"))
      (node (ref "C93") (pin "1") (pinfunction "1_1") (pintype "input"))
      (node (ref "DC2") (pin "1") (pinfunction "1_1") (pintype "unspecified"))
      (node (ref "J1") (pin "4") (pinfunction "4_4") (pintype "input"))
      (node (ref "J2") (pin "4") (pinfunction "4_4") (pintype "input"))
      (node (ref "J3") (pin "4") (pinfunction "4_4") (pintype "input"))
      (node (ref "J4") (pin "4") (pinfunction "4_4") (pintype "input"))
      (node (ref "J5") (pin "1") (pinfunction "1_1") (pintype "input"))
      (node (ref "J5") (pin "4") (pinfunction "4_4") (pintype "input"))
      (node (ref "LED1") (pin "1") (pinfunction "K_1") (pintype "unspecified"))
      (node (ref "LED2") (pin "1") (pinfunction "K_1") (pintype "unspecified"))
      (node (ref "PS2") (pin "3") (pinfunction "3_3") (pintype "unspecified"))
      (node (ref "PS2") (pin "4") (pinfunction "4_4") (pintype "unspecified"))
      (node (ref "PS2") (pin "7") (pinfunction "7_7") (pintype "unspecified"))
      (node (ref "PS2") (pin "8") (pinfunction "8_8") (pintype "unspecified"))
      (node (ref "PS2") (pin "9") (pinfunction "9_9") (pintype "unspecified"))
      (node (ref "Q1") (pin "2") (pinfunction "E_2") (pintype "unspecified"))
      (node (ref "Q2") (pin "2") (pinfunction "E_2") (pintype "unspecified"))
      (node (ref "R121") (pin "1") (pinfunction "1_1") (pintype "input"))
      (node (ref "R123") (pin "1") (pinfunction "1_1") (pintype "input"))
      (node (ref "R129") (pin "1") (pinfunction "1_1") (pintype "input"))
      (node (ref "R132") (pin "1") (pinfunction "1_1") (pintype "input"))
      (node (ref "R139") (pin "2") (pinfunction "2_2") (pintype "input"))
      (node (ref "SW1") (pin "2") (pinfunction "2_2") (pintype "input"))
      (node (ref "SW2") (pin "2") (pinfunction "2_2") (pintype "input"))
      (node (ref "SW3") (pin "2") (pinfunction "2_2") (pintype "input"))
      (node (ref "SW4") (pin "2") (pinfunction "2_2") (pintype "input"))
      (node (ref "SW5") (pin "2") (pinfunction "C_2") (pintype "input"))
      (node (ref "SW5") (pin "5") (pinfunction "SW_5") (pintype "input"))
      (node (ref "SW6") (pin "2") (pinfunction "C_2") (pintype "input"))
      (node (ref "SW6") (pin "4") (pinfunction "SW_4") (pintype "input"))
      (node (ref "U32") (pin "20") (pinfunction "AGND_20") (pintype "input"))
      (node (ref "U32") (pin "40") (pinfunction "DGND_40") (pintype "input"))
      (node (ref "U33") (pin "1") (pinfunction "GND_1") (pintype "input"))
      (node (ref "U40") (pin "4") (pinfunction "VCC-/GND_4") (pintype "unspecified"))
      (node (ref "U41") (pin "4") (pinfunction "VCC-/GND_4") (pintype "unspecified"))
      (node (ref "U42") (pin "4") (pinfunction "VCC-/GND_4") (pintype "unspecified"))
      (node (ref "VR1") (pin "1") (pinfunction "1_1") (pintype "input"))
      (node (ref "VR2") (pin "1") (pinfunction "1_1") (pintype "input"))
      (node (ref "VR3") (pin "1") (pinfunction "1_1") (pintype "input"))
      (node (ref "VR4") (pin "1") (pinfunction "1_1") (pintype "input"))
      (node (ref "VR5") (pin "1") (pinfunction "1_1") (pintype "input"))
      (node (ref "VR6") (pin "1") (pinfunction "1_1") (pintype "input"))
    )
    (net (code "15") (name "IN_L") (class "Default")
      (node (ref "U32") (pin "16") (pinfunction "AIN_L_16") (pintype "input"))
      (node (ref "U41") (pin "1") (pinfunction "OUT1_1") (pintype "output"))
      (node (ref "U41") (pin "2") (pinfunction "IN1-_2") (pintype "unspecified"))
    )
    (net (code "16") (name "IN_R") (class "Default")
      (node (ref "U32") (pin "17") (pinfunction "AIN_R_17") (pintype "input"))
      (node (ref "U41") (pin "6") (pinfunction "IN2-_6") (pintype "unspecified"))
      (node (ref "U41") (pin "7") (pinfunction "OUT2_7") (pintype "output"))
    )
    (net (code "17") (name "JIL_IN") (class "Default")
      (node (ref "J1") (pin "3") (pinfunction "3_3") (pintype "input"))
      (node (ref "U32") (pin "14") (pinfunction "D13_14") (pintype "input"))
    )
    (net (code "18") (name "JIR_IN") (class "Default")
      (node (ref "J2") (pin "3") (pinfunction "3_3") (pintype "input"))
      (node (ref "U32") (pin "15") (pinfunction "D14_15") (pintype "input"))
    )
    (net (code "19") (name "JI_L") (class "Default")
      (node (ref "C85") (pin "1") (pinfunction "1_1") (pintype "unspecified"))
      (node (ref "R129") (pin "2") (pinfunction "2_2") (pintype "input"))
      (node (ref "RL1") (pin "8") (pinfunction "8_8") (pintype "unspecified"))
    )
    (net (code "20") (name "JI_R") (class "Default")
      (node (ref "C87") (pin "1") (pinfunction "1_1") (pintype "unspecified"))
      (node (ref "R132") (pin "2") (pinfunction "2_2") (pintype "input"))
      (node (ref "RL2") (pin "8") (pinfunction "8_8") (pintype "unspecified"))
    )
    (net (code "21") (name "JOL_IN") (class "Default")
      (node (ref "J3") (pin "3") (pinfunction "3_3") (pintype "input"))
      (node (ref "U32") (pin "31") (pinfunction "A9/D24_31") (pintype "input"))
    )
    (net (code "22") (name "JOR_IN") (class "Default")
      (node (ref "J4") (pin "3") (pinfunction "3_3") (pintype "input"))
      (node (ref "U32") (pin "30") (pinfunction "A8/D23_30") (pintype "input"))
    )
    (net (code "23") (name "JO_L") (class "Default")
      (node (ref "R122") (pin "2") (pinfunction "2_2") (pintype "input"))
      (node (ref "RL1") (pin "9") (pinfunction "9_9") (pintype "unspecified"))
    )
    (net (code "24") (name "JO_R") (class "Default")
      (node (ref "R120") (pin "2") (pinfunction "2_2") (pintype "input"))
      (node (ref "RL2") (pin "9") (pinfunction "9_9") (pintype "unspecified"))
    )
    (net (code "25") (name "MISO") (class "Default")
      (node (ref "U32") (pin "10") (pinfunction "D9_10") (pintype "input"))
    )
    (net (code "26") (name "MOSI") (class "Default")
      (node (ref "U32") (pin "11") (pinfunction "D10_11") (pintype "input"))
      (node (ref "U33") (pin "4") (pinfunction "SDA_4") (pintype "input"))
    )
    (net (code "27") (name "Net-(C79-Pad2)") (class "Default")
      (node (ref "C79") (pin "2") (pinfunction "2_2") (pintype "unspecified"))
      (node (ref "R120") (pin "1") (pinfunction "1_1") (pintype "input"))
      (node (ref "R121") (pin "2") (pinfunction "2_2") (pintype "input"))
    )
    (net (code "28") (name "Net-(C80-Pad2)") (class "Default")
      (node (ref "C80") (pin "2") (pinfunction "2_2") (pintype "unspecified"))
      (node (ref "R122") (pin "1") (pinfunction "1_1") (pintype "input"))
      (node (ref "R123") (pin "2") (pinfunction "2_2") (pintype "input"))
    )
    (net (code "29") (name "Net-(C81-Pad1)") (class "Default")
      (node (ref "C81") (pin "1") (pinfunction "1_1") (pintype "input"))
      (node (ref "C83") (pin "1") (pinfunction "1_1") (pintype "unspecified"))
      (node (ref "R126") (pin "2") (pinfunction "2_2") (pintype "input"))
    )
    (net (code "30") (name "Net-(C82-Pad1)") (class "Default")
      (node (ref "C82") (pin "1") (pinfunction "1_1") (pintype "unspecified"))
      (node (ref "C84") (pin "1") (pinfunction "1_1") (pintype "input"))
      (node (ref "R127") (pin "2") (pinfunction "2_2") (pintype "input"))
    )
    (net (code "31") (name "Net-(C85-Pad2)") (class "Default")
      (node (ref "C85") (pin "2") (pinfunction "2_2") (pintype "unspecified"))
      (node (ref "R128") (pin "2") (pinfunction "2_2") (pintype "input"))
      (node (ref "R130") (pin "1") (pinfunction "1_1") (pintype "input"))
    )
    (net (code "32") (name "Net-(C87-Pad2)") (class "Default")
      (node (ref "C87") (pin "2") (pinfunction "2_2") (pintype "unspecified"))
      (node (ref "R131") (pin "2") (pinfunction "2_2") (pintype "input"))
      (node (ref "R133") (pin "1") (pinfunction "1_1") (pintype "input"))
    )
    (net (code "33") (name "Net-(J1-Pad6)") (class "Default")
      (node (ref "J1") (pin "6") (pinfunction "6_6") (pintype "input"))
      (node (ref "RL1") (pin "4") (pinfunction "4_4") (pintype "unspecified"))
    )
    (net (code "34") (name "Net-(J2-Pad6)") (class "Default")
      (node (ref "J2") (pin "6") (pinfunction "6_6") (pintype "input"))
      (node (ref "RL2") (pin "4") (pinfunction "4_4") (pintype "unspecified"))
    )
    (net (code "35") (name "Net-(J3-Pad6)") (class "Default")
      (node (ref "J3") (pin "6") (pinfunction "6_6") (pintype "input"))
      (node (ref "RL1") (pin "13") (pinfunction "13_13") (pintype "unspecified"))
    )
    (net (code "36") (name "Net-(J4-Pad6)") (class "Default")
      (node (ref "J4") (pin "6") (pinfunction "6_6") (pintype "input"))
      (node (ref "RL2") (pin "13") (pinfunction "13_13") (pintype "unspecified"))
    )
    (net (code "37") (name "Net-(LED1-A)") (class "Default")
      (node (ref "LED1") (pin "2") (pinfunction "A_2") (pintype "unspecified"))
      (node (ref "R142") (pin "1") (pinfunction "1_1") (pintype "input"))
    )
    (net (code "38") (name "Net-(LED2-A)") (class "Default")
      (node (ref "LED2") (pin "2") (pinfunction "A_2") (pintype "unspecified"))
      (node (ref "R143") (pin "1") (pinfunction "1_1") (pintype "input"))
    )
    (net (code "39") (name "Net-(Q1-B)") (class "Default")
      (node (ref "Q1") (pin "1") (pinfunction "B_1") (pintype "unspecified"))
      (node (ref "R140") (pin "2") (pinfunction "2_2") (pintype "input"))
    )
    (net (code "40") (name "Net-(Q2-B)") (class "Default")
      (node (ref "Q2") (pin "1") (pinfunction "B_1") (pintype "unspecified"))
      (node (ref "R141") (pin "2") (pinfunction "2_2") (pintype "input"))
    )
    (net (code "41") (name "Net-(RL1-Pad11)") (class "Default")
      (node (ref "RL1") (pin "11") (pinfunction "11_11") (pintype "unspecified"))
      (node (ref "RL1") (pin "6") (pinfunction "6_6") (pintype "unspecified"))
    )
    (net (code "42") (name "Net-(RL2-Pad11)") (class "Default")
      (node (ref "RL2") (pin "11") (pinfunction "11_11") (pintype "unspecified"))
      (node (ref "RL2") (pin "6") (pinfunction "6_6") (pintype "unspecified"))
    )
    (net (code "43") (name "Net-(SW5-A)") (class "Default")
      (node (ref "R108") (pin "2") (pinfunction "2_2") (pintype "input"))
      (node (ref "R113") (pin "2") (pinfunction "2_2") (pintype "input"))
      (node (ref "SW5") (pin "1") (pinfunction "A_1") (pintype "input"))
    )
    (net (code "44") (name "Net-(SW5-B)") (class "Default")
      (node (ref "R107") (pin "2") (pinfunction "2_2") (pintype "input"))
      (node (ref "R112") (pin "2") (pinfunction "2_2") (pintype "input"))
      (node (ref "SW5") (pin "3") (pinfunction "B_3") (pintype "input"))
    )
    (net (code "45") (name "Net-(SW6-A)") (class "Default")
      (node (ref "R106") (pin "2") (pinfunction "2_2") (pintype "input"))
      (node (ref "R114") (pin "1") (pinfunction "1_1") (pintype "input"))
      (node (ref "SW6") (pin "1") (pinfunction "A_1") (pintype "input"))
    )
    (net (code "46") (name "Net-(SW6-B)") (class "Default")
      (node (ref "R109") (pin "2") (pinfunction "2_2") (pintype "input"))
      (node (ref "R115") (pin "1") (pinfunction "1_1") (pintype "input"))
      (node (ref "SW6") (pin "3") (pinfunction "B_3") (pintype "input"))
    )
    (net (code "47") (name "Net-(U32-A10{slash}D25)") (class "Default")
      (node (ref "R142") (pin "2") (pinfunction "2_2") (pintype "input"))
      (node (ref "U32") (pin "32") (pinfunction "A10/D25_32") (pintype "input"))
    )
    (net (code "48") (name "Net-(U32-D0)") (class "Default")
      (node (ref "R140") (pin "1") (pinfunction "1_1") (pintype "input"))
      (node (ref "R141") (pin "1") (pinfunction "1_1") (pintype "input"))
      (node (ref "U32") (pin "1") (pinfunction "D0_1") (pintype "input"))
    )
    (net (code "49") (name "Net-(U32-D26)") (class "Default")
      (node (ref "R143") (pin "2") (pinfunction "2_2") (pintype "input"))
      (node (ref "U32") (pin "33") (pinfunction "D26_33") (pintype "input"))
    )
    (net (code "50") (name "Net-(U40A-IN1+)") (class "Default")
      (node (ref "C82") (pin "2") (pinfunction "2_2") (pintype "unspecified"))
      (node (ref "R124") (pin "2") (pinfunction "2_2") (pintype "input"))
      (node (ref "U40") (pin "3") (pinfunction "IN1+_3") (pintype "unspecified"))
    )
    (net (code "51") (name "Net-(U40A-IN1-)") (class "Default")
      (node (ref "C79") (pin "1") (pinfunction "1_1") (pintype "unspecified"))
      (node (ref "U40") (pin "1") (pinfunction "OUT1_1") (pintype "output"))
      (node (ref "U40") (pin "2") (pinfunction "IN1-_2") (pintype "unspecified"))
    )
    (net (code "52") (name "Net-(U40B-IN2+)") (class "Default")
      (node (ref "C83") (pin "2") (pinfunction "2_2") (pintype "unspecified"))
      (node (ref "R125") (pin "2") (pinfunction "2_2") (pintype "input"))
      (node (ref "U40") (pin "5") (pinfunction "IN2+_5") (pintype "unspecified"))
    )
    (net (code "53") (name "Net-(U40B-IN2-)") (class "Default")
      (node (ref "C80") (pin "1") (pinfunction "1_1") (pintype "unspecified"))
      (node (ref "U40") (pin "6") (pinfunction "IN2-_6") (pintype "unspecified"))
      (node (ref "U40") (pin "7") (pinfunction "OUT2_7") (pintype "output"))
    )
    (net (code "54") (name "Net-(U41A-IN1+)") (class "Default")
      (node (ref "C86") (pin "2") (pinfunction "2_2") (pintype "input"))
      (node (ref "R130") (pin "2") (pinfunction "2_2") (pintype "input"))
      (node (ref "U41") (pin "3") (pinfunction "IN1+_3") (pintype "unspecified"))
    )
    (net (code "55") (name "Net-(U41B-IN2+)") (class "Default")
      (node (ref "C88") (pin "2") (pinfunction "2_2") (pintype "input"))
      (node (ref "R133") (pin "2") (pinfunction "2_2") (pintype "input"))
      (node (ref "U41") (pin "5") (pinfunction "IN2+_5") (pintype "unspecified"))
    )
    (net (code "56") (name "Net-(U42A-IN1-)") (class "Default")
      (node (ref "U42") (pin "1") (pinfunction "OUT1_1") (pintype "output"))
      (node (ref "U42") (pin "2") (pinfunction "IN1-_2") (pintype "unspecified"))
    )
    (net (code "57") (name "Net-(U42B-IN2+)") (class "Default")
      (node (ref "C89") (pin "1") (pinfunction "1_1") (pintype "input"))
      (node (ref "R138") (pin "2") (pinfunction "2_2") (pintype "input"))
      (node (ref "R139") (pin "1") (pinfunction "1_1") (pintype "input"))
      (node (ref "U42") (pin "5") (pinfunction "IN2+_5") (pintype "unspecified"))
    )
    (net (code "58") (name "OUT_L") (class "Default")
      (node (ref "R126") (pin "1") (pinfunction "1_1") (pintype "input"))
      (node (ref "U32") (pin "18") (pinfunction "AOUT_L_18") (pintype "input"))
    )
    (net (code "59") (name "OUT_R") (class "Default")
      (node (ref "R127") (pin "1") (pinfunction "1_1") (pintype "input"))
      (node (ref "U32") (pin "19") (pinfunction "AOUT_R_19") (pintype "input"))
    )
    (net (code "60") (name "POT1") (class "Default")
      (node (ref "U32") (pin "22") (pinfunction "A0/D15_22") (pintype "input"))
      (node (ref "VR1") (pin "2") (pinfunction "2_2") (pintype "input"))
    )
    (net (code "61") (name "POT2") (class "Default")
      (node (ref "U32") (pin "23") (pinfunction "A1/D16_23") (pintype "input"))
      (node (ref "VR2") (pin "2") (pinfunction "2_2") (pintype "input"))
    )
    (net (code "62") (name "POT3") (class "Default")
      (node (ref "U32") (pin "24") (pinfunction "A2/D17_24") (pintype "input"))
      (node (ref "VR3") (pin "2") (pinfunction "2_2") (pintype "input"))
    )
    (net (code "63") (name "POT4") (class "Default")
      (node (ref "U32") (pin "25") (pinfunction "A3/D18_25") (pintype "input"))
      (node (ref "VR4") (pin "2") (pinfunction "2_2") (pintype "input"))
    )
    (net (code "64") (name "POT5") (class "Default")
      (node (ref "U32") (pin "26") (pinfunction "A4/D19_26") (pintype "input"))
      (node (ref "VR5") (pin "2") (pinfunction "2_2") (pintype "input"))
    )
    (net (code "65") (name "POT6") (class "Default")
      (node (ref "U32") (pin "27") (pinfunction "A5/D20_27") (pintype "input"))
      (node (ref "VR6") (pin "2") (pinfunction "2_2") (pintype "input"))
    )
    (net (code "66") (name "RLY1") (class "Default")
      (node (ref "D1") (pin "2") (pinfunction "A_2") (pintype "unspecified"))
      (node (ref "Q1") (pin "3") (pinfunction "C_3") (pintype "unspecified"))
      (node (ref "RL1") (pin "16") (pinfunction "16_16") (pintype "unspecified"))
    )
    (net (code "67") (name "RLY2") (class "Default")
      (node (ref "D2") (pin "2") (pinfunction "A_2") (pintype "unspecified"))
      (node (ref "Q2") (pin "3") (pinfunction "C_3") (pintype "unspecified"))
      (node (ref "RL2") (pin "16") (pinfunction "16_16") (pintype "unspecified"))
    )
    (net (code "68") (name "RST") (class "Default")
      (node (ref "U32") (pin "12") (pinfunction "D11_12") (pintype "input"))
      (node (ref "U33") (pin "5") (pinfunction "RST_5") (pintype "input"))
    )
    (net (code "69") (name "SCK") (class "Default")
      (node (ref "U32") (pin "9") (pinfunction "D8_9") (pintype "input"))
      (node (ref "U33") (pin "3") (pinfunction "SCL_3") (pintype "input"))
    )
    (net (code "70") (name "SW1") (class "Default")
      (node (ref "PS2") (pin "1") (pinfunction "1_1") (pintype "unspecified"))
      (node (ref "SW1") (pin "1") (pinfunction "1_1") (pintype "input"))
      (node (ref "U32") (pin "34") (pinfunction "D27_34") (pintype "input"))
    )
    (net (code "71") (name "SW2") (class "Default")
      (node (ref "PS2") (pin "2") (pinfunction "2_2") (pintype "unspecified"))
      (node (ref "SW2") (pin "1") (pinfunction "1_1") (pintype "input"))
      (node (ref "U32") (pin "35") (pinfunction "A11/D28_35") (pintype "input"))
    )
    (net (code "72") (name "SW3") (class "Default")
      (node (ref "PS2") (pin "5") (pinfunction "5_5") (pintype "unspecified"))
      (node (ref "SW3") (pin "1") (pinfunction "1_1") (pintype "input"))
      (node (ref "U32") (pin "36") (pinfunction "D29_36") (pintype "input"))
    )
    (net (code "73") (name "SW4") (class "Default")
      (node (ref "PS2") (pin "6") (pinfunction "6_6") (pintype "unspecified"))
      (node (ref "SW4") (pin "1") (pinfunction "1_1") (pintype "input"))
      (node (ref "U32") (pin "37") (pinfunction "D30_37") (pintype "input"))
    )
    (net (code "74") (name "VREF") (class "Default")
      (node (ref "C86") (pin "1") (pinfunction "1_1") (pintype "input"))
      (node (ref "C88") (pin "1") (pinfunction "1_1") (pintype "input"))
      (node (ref "R124") (pin "1") (pinfunction "1_1") (pintype "input"))
      (node (ref "R125") (pin "1") (pinfunction "1_1") (pintype "input"))
      (node (ref "R128") (pin "1") (pinfunction "1_1") (pintype "input"))
      (node (ref "R131") (pin "1") (pinfunction "1_1") (pintype "input"))
      (node (ref "U42") (pin "3") (pinfunction "IN1+_3") (pintype "unspecified"))
      (node (ref "U42") (pin "6") (pinfunction "IN2-_6") (pintype "unspecified"))
      (node (ref "U42") (pin "7") (pinfunction "OUT2_7") (pintype "output"))
    )
    (net (code "75") (name "unconnected-(DC2-Pad3)") (class "Default")
      (node (ref "DC2") (pin "3") (pinfunction "3_3") (pintype "unspecified+no_connect"))
    )
    (net (code "76") (name "unconnected-(J1-Pad1)") (class "Default")
      (node (ref "J1") (pin "1") (pinfunction "1_1") (pintype "input"))
    )
    (net (code "77") (name "unconnected-(J1-Pad2)") (class "Default")
      (node (ref "J1") (pin "2") (pinfunction "2_2") (pintype "input"))
    )
    (net (code "78") (name "unconnected-(J1-Pad5)") (class "Default")
      (node (ref "J1") (pin "5") (pinfunction "5_5") (pintype "input"))
    )
    (net (code "79") (name "unconnected-(J2-Pad1)") (class "Default")
      (node (ref "J2") (pin "1") (pinfunction "1_1") (pintype "input"))
    )
    (net (code "80") (name "unconnected-(J2-Pad2)") (class "Default")
      (node (ref "J2") (pin "2") (pinfunction "2_2") (pintype "input"))
    )
    (net (code "81") (name "unconnected-(J2-Pad5)") (class "Default")
      (node (ref "J2") (pin "5") (pinfunction "5_5") (pintype "input"))
    )
    (net (code "82") (name "unconnected-(J3-Pad1)") (class "Default")
      (node (ref "J3") (pin "1") (pinfunction "1_1") (pintype "input"))
    )
    (net (code "83") (name "unconnected-(J3-Pad2)") (class "Default")
      (node (ref "J3") (pin "2") (pinfunction "2_2") (pintype "input"))
    )
    (net (code "84") (name "unconnected-(J3-Pad5)") (class "Default")
      (node (ref "J3") (pin "5") (pinfunction "5_5") (pintype "input"))
    )
    (net (code "85") (name "unconnected-(J4-Pad1)") (class "Default")
      (node (ref "J4") (pin "1") (pinfunction "1_1") (pintype "input"))
    )
    (net (code "86") (name "unconnected-(J4-Pad2)") (class "Default")
      (node (ref "J4") (pin "2") (pinfunction "2_2") (pintype "input"))
    )
    (net (code "87") (name "unconnected-(J4-Pad5)") (class "Default")
      (node (ref "J4") (pin "5") (pinfunction "5_5") (pintype "input"))
    )
    (net (code "88") (name "unconnected-(J5-Pad2)") (class "Default")
      (node (ref "J5") (pin "2") (pinfunction "2_2") (pintype "input"))
    )
  )
)
